# CANBUS.net
KiCad netlist of a schematic drawn in Altium Designer
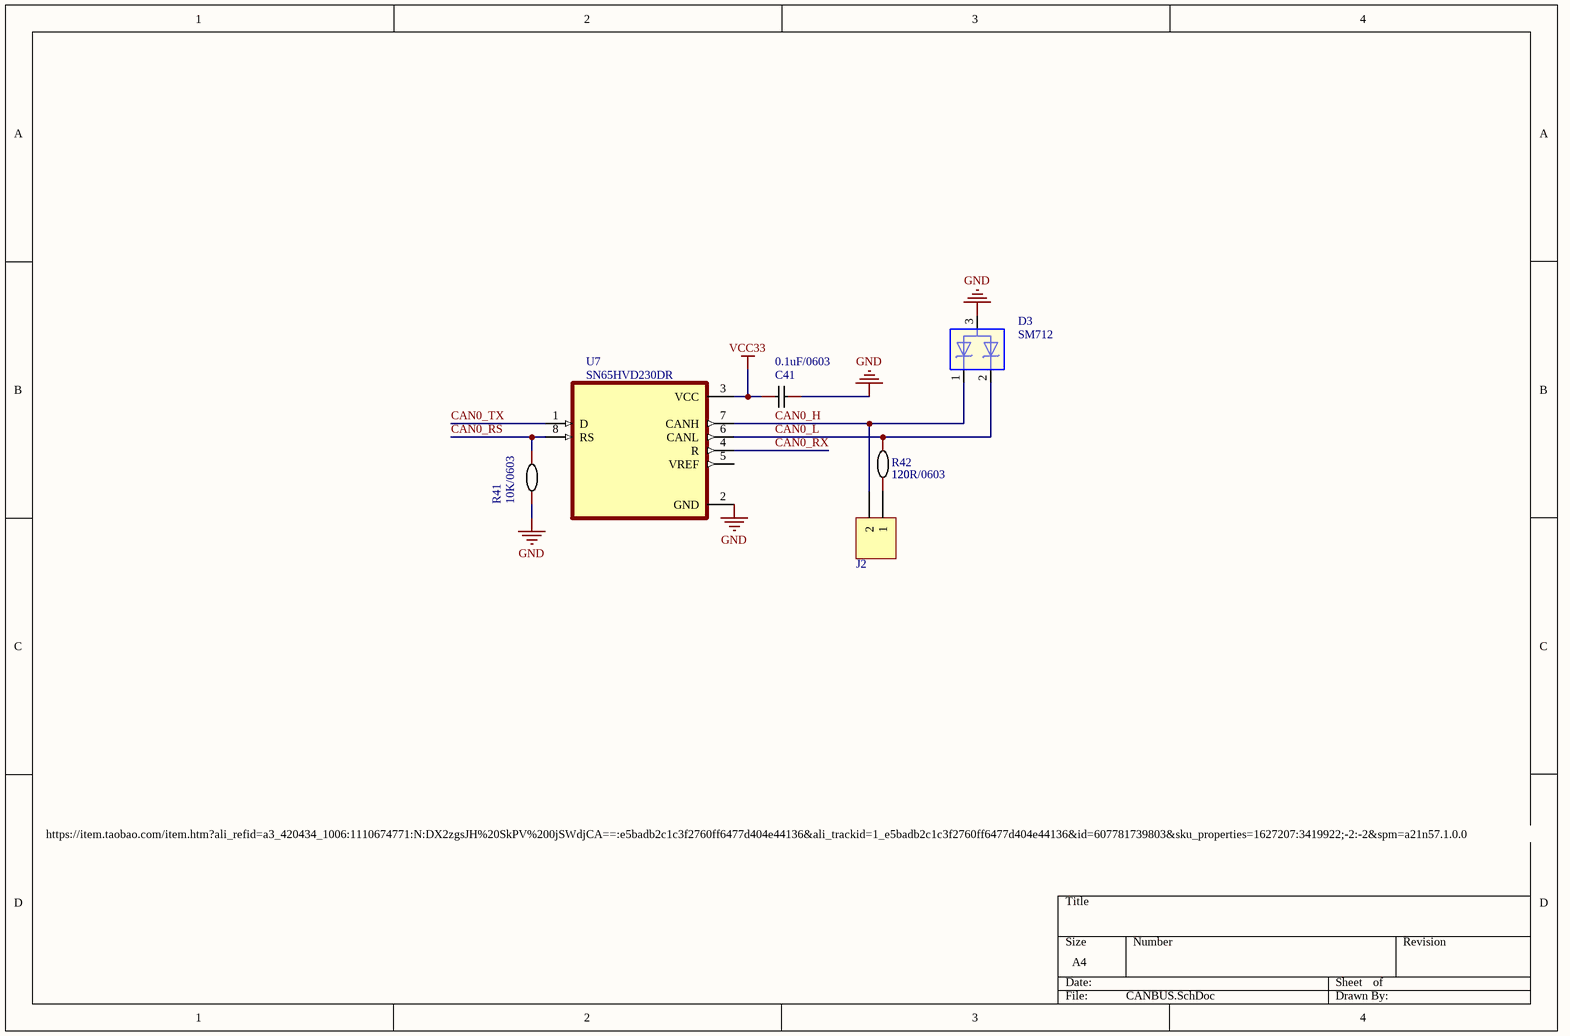
[diagram p0: CANBUS.SchDoc]

(export (version "E")
  (design (tool "Eeschema 10.0.6"))
  (components
    (comp (ref "C41")
      (value "0.1uF/0603")
      (footprint "CAP0603")
      (fields (field (name "MANUFACTURER PART") "CL05B104KO5NNNC") (field (name "MANUFACTURER") "SAMSUNG"))
      (libsource (lib "altium-import") (part "root_2_100nF_"))
    )
    (comp (ref "D3")
      (value "SM712")
      (footprint "SOT95P280X135-3N")
      (description "兩路TVS二极管阵列")
      (fields (field (name "PART NUMBER") "702112964"))
      (libsource (lib "*") (part "SM05_D24"))
    )
    (comp (ref "J2")
      (value "Jumper")
      (footprint "HDR1X2")
      (description "Header, 2-Pin")
      (fields (field (name "PUBLISHER") "Altium Limited"))
      (libsource (lib "Miscellaneous Connectors") (part "Header 2"))
    )
    (comp (ref "R41")
      (value "10K/0603")
      (footprint "RES0603")
      (fields (field (name "MANUFACTURER") "UniOhm") (field (name "MANUFACTURER PART") "0402WGF1002TCE"))
      (libsource (lib "altium-import") (part "root_1_10K_"))
    )
    (comp (ref "R42")
      (value "120R/0603")
      (footprint "RES0603")
      (fields
        (field (name "NAME") "120")
        (field (name "MANUFACTURER") "RALEC")
        (field (name "MANUFACTURER PART") "RTT061200FTP")
      )
      (libsource (lib "altium-import") (part "root_3_120_"))
    )
    (comp (ref "U7")
      (value "SN65HVD230DR")
      (footprint "SN65HVD230DR")
      (description "3.3 V CAN Transceiver with Standby Mode")
      (fields (field (name "MF") "Texas Instruments"))
      (libsource (lib "ESPC6IOTALLinOne") (part "SN65HVD230DR"))
    )
  )
  (nets
    (net (code "1") (name "/CAN0_H") (class "Default")
      (node (ref "D3") (pin "1") (pinfunction "1_1") (pintype "passive"))
      (node (ref "J2") (pin "2") (pinfunction "2_2") (pintype "passive"))
      (node (ref "U7") (pin "7") (pinfunction "CANH_7") (pintype "output"))
    )
    (net (code "2") (name "/CAN0_L") (class "Default")
      (node (ref "D3") (pin "2") (pinfunction "2_2") (pintype "passive"))
      (node (ref "R42") (pin "1") (pinfunction "1_1") (pintype "passive"))
      (node (ref "U7") (pin "6") (pinfunction "CANL_6") (pintype "output"))
    )
    (net (code "3") (name "/CAN0_RS") (class "Default")
      (node (ref "R41") (pin "2") (pinfunction "2_2") (pintype "passive"))
      (node (ref "U7") (pin "8") (pinfunction "RS_8") (pintype "input"))
    )
    (net (code "4") (name "/CAN0_RX") (class "Default")
      (node (ref "U7") (pin "4") (pinfunction "R_4") (pintype "output"))
    )
    (net (code "5") (name "/CAN0_TX") (class "Default")
      (node (ref "U7") (pin "1") (pinfunction "D_1") (pintype "input"))
    )
    (net (code "6") (name "GND") (class "Default")
      (node (ref "C41") (pin "1") (pinfunction "1_1") (pintype "passive"))
      (node (ref "D3") (pin "3") (pinfunction "3_3") (pintype "passive"))
      (node (ref "R41") (pin "1") (pinfunction "1_1") (pintype "passive"))
      (node (ref "U7") (pin "2") (pinfunction "GND_2") (pintype "power_in"))
    )
    (net (code "7") (name "Net-(J2-Pad1)") (class "Default")
      (node (ref "J2") (pin "1") (pinfunction "1_1") (pintype "passive"))
      (node (ref "R42") (pin "2") (pinfunction "2_2") (pintype "passive"))
    )
    (net (code "8") (name "VCC33") (class "Default")
      (node (ref "C41") (pin "2") (pinfunction "2_2") (pintype "passive"))
      (node (ref "U7") (pin "3") (pinfunction "VCC_3") (pintype "power_in"))
    )
    (net (code "9") (name "unconnected-(U7-VREF-Pad5)") (class "Default")
      (node (ref "U7") (pin "5") (pinfunction "VREF_5") (pintype "output"))
    )
  )
)
